# PowerSupply.net
KiCad netlist of a schematic drawn in Altium Designer
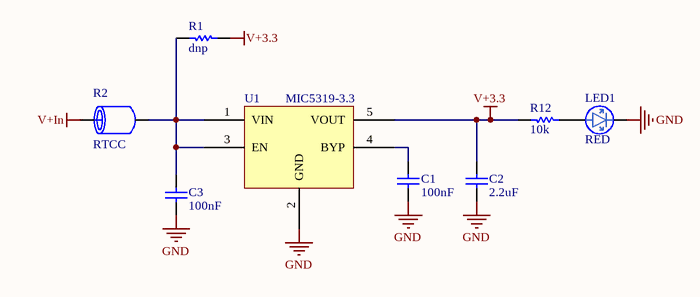
[diagram p0: PowerSupply.SchDoc]

(export (version "E")
  (design (tool "Eeschema 10.0.6"))
  (components
    (comp (ref "C1")
      (value "100nF")
      (footprint "0603")
      (description "Capacitor (Semiconductor SIM Model)")
      (fields (field (name "PUBLISHER") "Altium Limited"))
      (libsource (lib "Miscellaneous Devices") (part "Cap Semi"))
    )
    (comp (ref "C2")
      (value "2.2uF")
      (footprint "0805")
      (description "Capacitor (Semiconductor SIM Model)")
      (fields (field (name "PUBLISHER") "Altium Limited"))
      (libsource (lib "Miscellaneous Devices") (part "Cap Semi"))
    )
    (comp (ref "C3")
      (value "100nF")
      (footprint "0603")
      (description "Capacitor (Semiconductor SIM Model)")
      (fields (field (name "PUBLISHER") "Altium Limited"))
      (libsource (lib "Miscellaneous Devices") (part "Cap Semi"))
    )
    (comp (ref "LED1")
      (value "RED")
      (footprint "LED-0603-RED")
      (libsource (lib "Library_Schematic") (part "SMD_LED_0805"))
    )
    (comp (ref "R1")
      (value "dnp")
      (footprint "0603")
      (description "Semiconductor Resistor")
      (fields (field (name "PUBLISHER") "Altium Limited"))
      (libsource (lib "Miscellaneous Devices") (part "Res Semi"))
    )
    (comp (ref "R2")
      (value "RTCC")
      (footprint "0805")
      (fields
        (field (name "MANUFACTURER") "MURATA")
        (field (name "MANUFACTURER PART NUMBER") "BLM18EG471SN1D")
      )
      (libsource (lib "AS3911") (part "Ferritbeat"))
    )
    (comp (ref "R12")
      (value "10k")
      (footprint "0603")
      (description "Semiconductor Resistor")
      (fields (field (name "PUBLISHER") "Altium Limited"))
      (libsource (lib "Miscellaneous Devices") (part "Res Semi"))
    )
    (comp (ref "U1") (value "MIC5319-3.3") (footprint "sot23-5") (libsource (lib "Schlib1") (part "MIC5305")))
  )
  (nets
    (net (code "1") (name "GND") (class "Default")
      (node (ref "C1") (pin "1") (pinfunction "1_1") (pintype "passive"))
      (node (ref "C2") (pin "1") (pinfunction "1_1") (pintype "passive"))
      (node (ref "C3") (pin "1") (pinfunction "1_1") (pintype "passive"))
      (node (ref "LED1") (pin "K") (pintype "passive"))
      (node (ref "U1") (pin "2") (pinfunction "GND_2") (pintype "passive"))
    )
    (net (code "2") (name "Net-(LED1-PadA)") (class "Default")
      (node (ref "LED1") (pin "A") (pintype "passive"))
      (node (ref "R12") (pin "1") (pinfunction "1_1") (pintype "passive"))
    )
    (net (code "3") (name "Net-(U1-BYP)") (class "Default")
      (node (ref "C1") (pin "2") (pinfunction "2_2") (pintype "passive"))
      (node (ref "U1") (pin "4") (pinfunction "BYP_4") (pintype "passive"))
    )
    (net (code "4") (name "Net-(U1-EN)") (class "Default")
      (node (ref "C3") (pin "2") (pinfunction "2_2") (pintype "passive"))
      (node (ref "R1") (pin "2") (pinfunction "2_2") (pintype "passive"))
      (node (ref "R2") (pin "2") (pinfunction "2_2") (pintype "passive"))
      (node (ref "U1") (pin "1") (pinfunction "VIN_1") (pintype "passive"))
      (node (ref "U1") (pin "3") (pinfunction "EN_3") (pintype "passive"))
    )
    (net (code "5") (name "V+3.3") (class "Default")
      (node (ref "C2") (pin "2") (pinfunction "2_2") (pintype "passive"))
      (node (ref "R1") (pin "1") (pinfunction "1_1") (pintype "passive"))
      (node (ref "R12") (pin "2") (pinfunction "2_2") (pintype "passive"))
      (node (ref "U1") (pin "5") (pinfunction "VOUT_5") (pintype "passive"))
    )
    (net (code "6") (name "V+In") (class "Default")
      (node (ref "R2") (pin "1") (pinfunction "1_1") (pintype "passive"))
    )
  )
)
